# mcu_power.net
KiCad netlist of a schematic drawn in Altium Designer
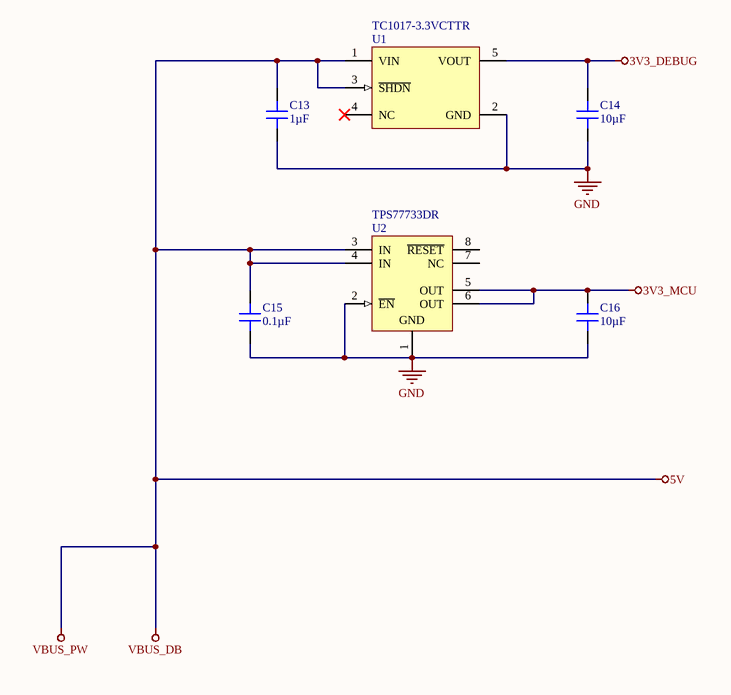
[diagram p0: mcu_power.SchDoc]

(export (version "E")
  (design (tool "Eeschema 10.0.6"))
  (components
    (comp (ref "C13")
      (value "1µF")
      (footprint "CAP 0603_1608")
      (description "CAP CER 0603 1UF 16V X7R 20%")
      (fields (field (name "PART NUMBER") "C0603X105M4RACAUTO") (field (name "MANUFACTURER") "KEMET"))
      (libsource (lib "Celestial Altium Library - altium_library (2)") (part "Capacitor"))
    )
    (comp (ref "C14")
      (value "10µF")
      (footprint "CAP 0603_1608")
      (description "CAP CER 10UF 16V X5R 0603")
      (fields
        (field (name "PART NUMBER") "GRT188R61C106KE13D")
        (field (name "MANUFACTURER") "Murata Electronics")
      )
      (libsource (lib "Celestial Altium Library - altium_library (2)") (part "Capacitor"))
    )
    (comp (ref "C15")
      (value "0.1µF")
      (footprint "CAP 0603_1608")
      (description "CAP CER 0.1UF 16V X7R 0603")
      (fields (field (name "PART NUMBER") "CS0603KRX7R7BB104") (field (name "MANUFACTURER") "Yageo"))
      (libsource (lib "Celestial Altium Library - altium_library (2)") (part "Capacitor"))
    )
    (comp (ref "C16")
      (value "10µF")
      (footprint "CAP 0603_1608")
      (description "CAP CER 10UF 16V X5R 0603")
      (fields
        (field (name "PART NUMBER") "GRT188R61C106KE13D")
        (field (name "MANUFACTURER") "Murata Electronics")
      )
      (libsource (lib "Celestial Altium Library - altium_library (2)") (part "Capacitor"))
    )
    (comp (ref "U1")
      (value "TC1017-3.3VCTTR")
      (footprint "SOT-23-CT5_L")
      (description "150 mA, Tiny CMOS LDO with Shutdown, 5-Pin SOT-23, Extended Temperature, Tape and Reel")
      (libsource (lib "Altium Content Vault") (part "PM-LINEREG-TC1017-IL5A"))
    )
    (comp (ref "U2")
      (value "TPS77733DR")
      (footprint "D0008A_N")
      (fields (field (name "MANUFACTURER") "Texas Instruments"))
      (libsource (lib "Altium Content Vault") (part "TI-TPS7XXXXD8"))
    )
  )
  (nets
    (net (code "1") (name "3V3_DEBUG") (class "Default")
      (node (ref "C14") (pin "2") (pinfunction "2_2") (pintype "passive"))
      (node (ref "U1") (pin "5") (pinfunction "VOUT_5") (pintype "power_in"))
    )
    (net (code "2") (name "3V3_MCU") (class "Default")
      (node (ref "C16") (pin "2") (pinfunction "2_2") (pintype "passive"))
      (node (ref "U2") (pin "5") (pinfunction "OUT_5") (pintype "power_in"))
      (node (ref "U2") (pin "6") (pinfunction "OUT_6") (pintype "power_in"))
    )
    (net (code "3") (name "5V") (class "Default")
      (node (ref "C13") (pin "2") (pinfunction "2_2") (pintype "passive"))
      (node (ref "C15") (pin "2") (pinfunction "2_2") (pintype "passive"))
      (node (ref "U1") (pin "1") (pinfunction "VIN_1") (pintype "power_in"))
      (node (ref "U1") (pin "3") (pinfunction "~{SHDN}_3") (pintype "input"))
      (node (ref "U2") (pin "3") (pinfunction "IN_3") (pintype "power_in"))
      (node (ref "U2") (pin "4") (pinfunction "IN_4") (pintype "power_in"))
    )
    (net (code "4") (name "GND") (class "Default")
      (node (ref "C13") (pin "1") (pinfunction "1_1") (pintype "passive"))
      (node (ref "C14") (pin "1") (pinfunction "1_1") (pintype "passive"))
      (node (ref "C15") (pin "1") (pinfunction "1_1") (pintype "passive"))
      (node (ref "C16") (pin "1") (pinfunction "1_1") (pintype "passive"))
      (node (ref "U1") (pin "2") (pinfunction "GND_2") (pintype "power_in"))
      (node (ref "U2") (pin "1") (pinfunction "GND_1") (pintype "power_in"))
      (node (ref "U2") (pin "2") (pinfunction "~{EN}_2") (pintype "input"))
    )
    (net (code "5") (name "unconnected-(U1-NC-Pad4)") (class "Default")
      (node (ref "U1") (pin "4") (pinfunction "NC_4") (pintype "passive+no_connect"))
    )
    (net (code "6") (name "unconnected-(U2-NC-Pad7)") (class "Default")
      (node (ref "U2") (pin "7") (pinfunction "NC_7") (pintype "passive"))
    )
    (net (code "7") (name "unconnected-(U2-~{RESET}-Pad8)") (class "Default")
      (node (ref "U2") (pin "8") (pinfunction "~{RESET}_8") (pintype "tri_state"))
    )
  )
)
